# powerSMALL_smaller.net
KiCad netlist of a schematic drawn in EAGLE
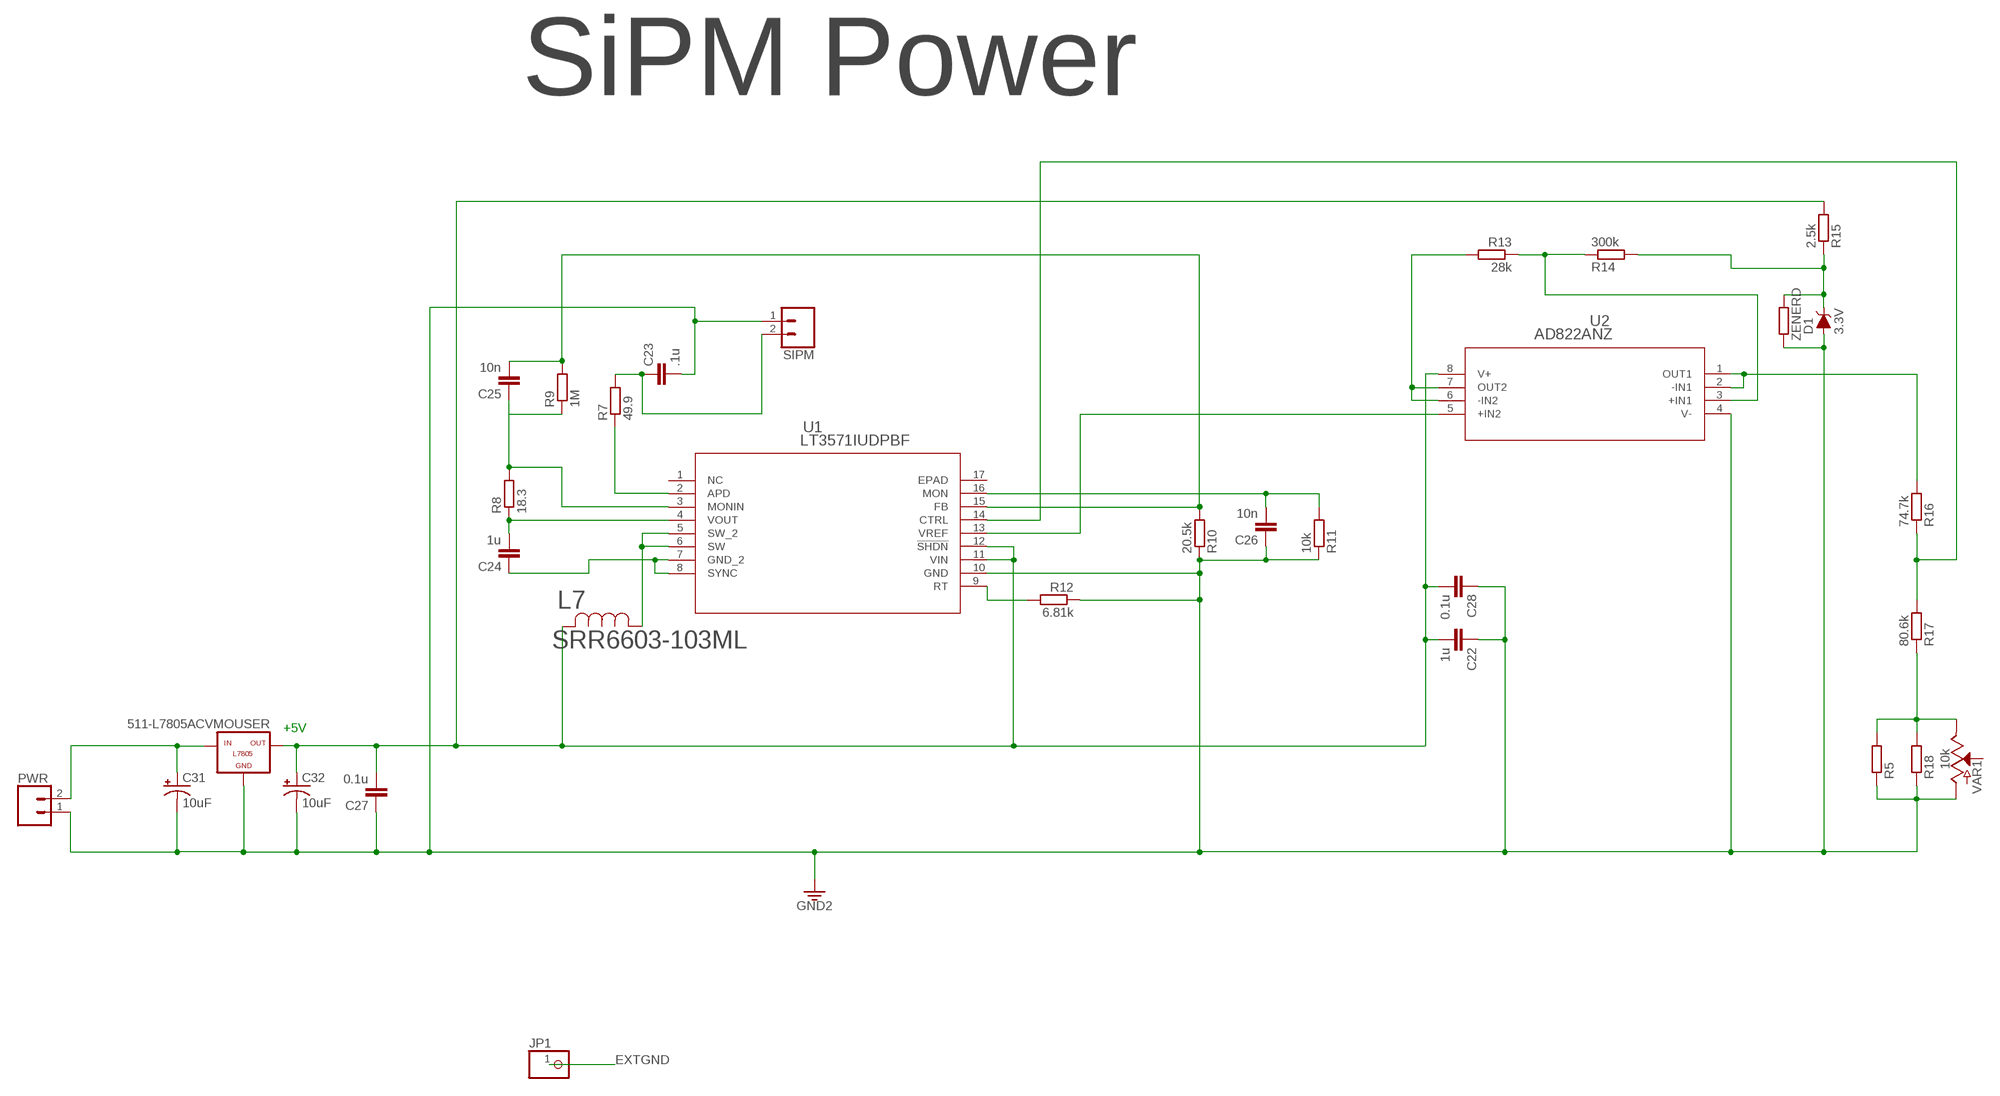
[diagram p0: schematic, sheet 1, part 1 of 2]
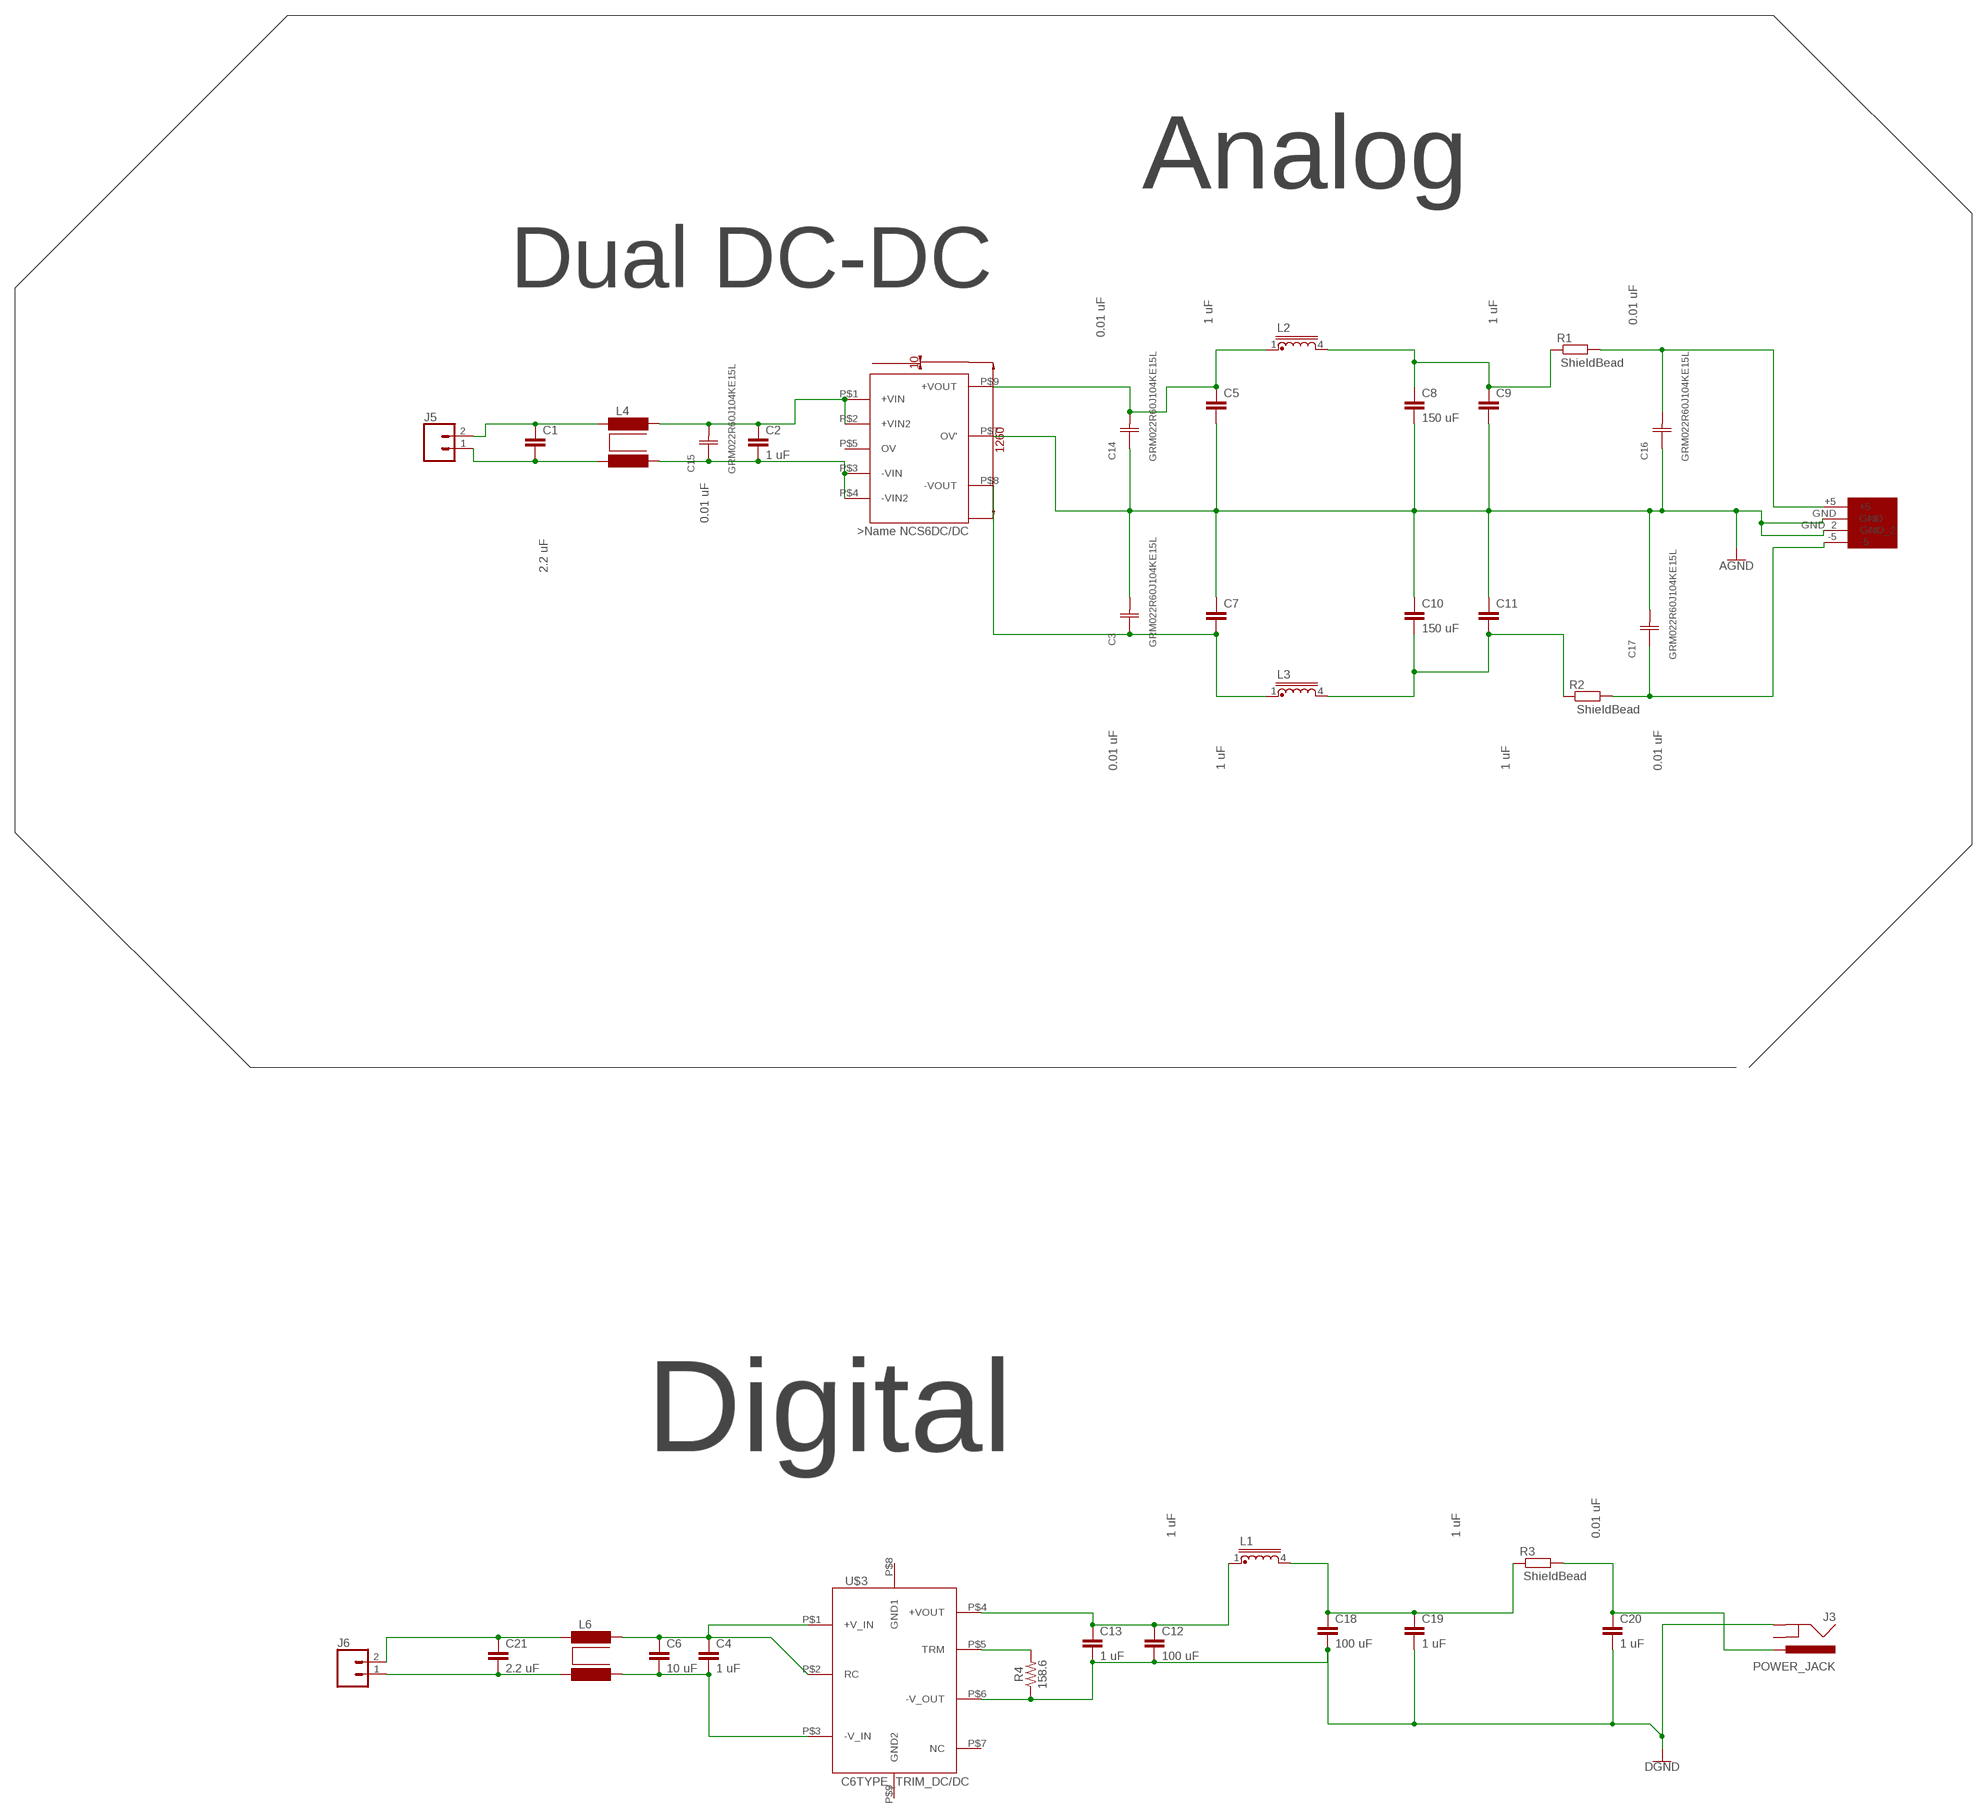
[diagram p1: schematic, sheet 1, part 2 of 2]

(export (version "E")
  (design (tool "Eeschema 10.0.6"))
  (components
    (comp (ref "511-L7805ACVMOUSER")
      (value "-L7805")
      (footprint "eagle-import:L7805")
      (libsource (lib "eagle-import") (part "-L7805"))
    )
    (comp (ref "C1")
      (value "C2.5/2")
      (footprint "eagle-import:C2.5-2")
      (libsource (lib "eagle-import") (part "C2.5/2"))
    )
    (comp (ref "C2")
      (value "1 uF")
      (footprint "eagle-import:CAP-PTH-10MM")
      (libsource (lib "eagle-import") (part "10NF-PTH-10MM-10000V-1-%"))
    )
    (comp (ref "C3")
      (value "GRM022R60J104KE15L")
      (footprint "eagle-import:CAP_GRM02L_P42XP22")
      (libsource (lib "eagle-import") (part "GRM022R60J104KE15L"))
    )
    (comp (ref "C4")
      (value "1 uF")
      (footprint "eagle-import:CAP-PTH-10MM")
      (libsource (lib "eagle-import") (part "10NF-PTH-10MM-10000V-1-%"))
    )
    (comp (ref "C5")
      (value "C2.5/2")
      (footprint "eagle-import:C2.5-2")
      (libsource (lib "eagle-import") (part "C2.5/2"))
    )
    (comp (ref "C6")
      (value "10 uF")
      (footprint "eagle-import:CAP-PTH-10MM")
      (libsource (lib "eagle-import") (part "10NF-PTH-10MM-10000V-1-%"))
    )
    (comp (ref "C7")
      (value "C2.5/2")
      (footprint "eagle-import:C2.5-2")
      (libsource (lib "eagle-import") (part "C2.5/2"))
    )
    (comp (ref "C8")
      (value "150 uF")
      (footprint "eagle-import:CAP-PTH-10MM")
      (libsource (lib "eagle-import") (part "10NF-PTH-10MM-10000V-1-%"))
    )
    (comp (ref "C9")
      (value "C2.5/2")
      (footprint "eagle-import:C2.5-2")
      (libsource (lib "eagle-import") (part "C2.5/2"))
    )
    (comp (ref "C10")
      (value "150 uF")
      (footprint "eagle-import:CAP-PTH-10MM")
      (libsource (lib "eagle-import") (part "10NF-PTH-10MM-10000V-1-%"))
    )
    (comp (ref "C11")
      (value "C2.5/2")
      (footprint "eagle-import:C2.5-2")
      (libsource (lib "eagle-import") (part "C2.5/2"))
    )
    (comp (ref "C12")
      (value "100 uF")
      (footprint "eagle-import:CAP-PTH-10MM")
      (libsource (lib "eagle-import") (part "10NF-PTH-10MM-10000V-1-%"))
    )
    (comp (ref "C13")
      (value "1 uF")
      (footprint "eagle-import:CAP-PTH-10MM")
      (libsource (lib "eagle-import") (part "10NF-PTH-10MM-10000V-1-%"))
    )
    (comp (ref "C14")
      (value "GRM022R60J104KE15L")
      (footprint "eagle-import:CAP_GRM02L_P42XP22")
      (libsource (lib "eagle-import") (part "GRM022R60J104KE15L"))
    )
    (comp (ref "C15")
      (value "GRM022R60J104KE15L")
      (footprint "eagle-import:CAP_GRM02L_P42XP22")
      (libsource (lib "eagle-import") (part "GRM022R60J104KE15L"))
    )
    (comp (ref "C16")
      (value "GRM022R60J104KE15L")
      (footprint "eagle-import:CAP_GRM02L_P42XP22")
      (libsource (lib "eagle-import") (part "GRM022R60J104KE15L"))
    )
    (comp (ref "C17")
      (value "GRM022R60J104KE15L")
      (footprint "eagle-import:CAP_GRM02L_P42XP22")
      (libsource (lib "eagle-import") (part "GRM022R60J104KE15L"))
    )
    (comp (ref "C18")
      (value "100 uF")
      (footprint "eagle-import:CAP-PTH-10MM")
      (libsource (lib "eagle-import") (part "10NF-PTH-10MM-10000V-1-%"))
    )
    (comp (ref "C19")
      (value "1 uF")
      (footprint "eagle-import:CAP-PTH-10MM")
      (libsource (lib "eagle-import") (part "10NF-PTH-10MM-10000V-1-%"))
    )
    (comp (ref "C20")
      (value "1 uF")
      (footprint "eagle-import:CAP-PTH-10MM")
      (libsource (lib "eagle-import") (part "10NF-PTH-10MM-10000V-1-%"))
    )
    (comp (ref "C21")
      (value "2.2 uF")
      (footprint "eagle-import:CAP-PTH-10MM")
      (libsource (lib "eagle-import") (part "10NF-PTH-10MM-10000V-1-%"))
    )
    (comp (ref "C22")
      (value "1u")
      (footprint "eagle-import:C2.5-2")
      (libsource (lib "eagle-import") (part "C2.5/2"))
    )
    (comp (ref "C23")
      (value ".1u")
      (footprint "eagle-import:C2.5-2")
      (libsource (lib "eagle-import") (part "C2.5/2"))
    )
    (comp (ref "C24")
      (value "1u")
      (footprint "eagle-import:C2.5-2")
      (libsource (lib "eagle-import") (part "C2.5/2"))
    )
    (comp (ref "C25")
      (value "10n")
      (footprint "eagle-import:C2.5-2")
      (libsource (lib "eagle-import") (part "C2.5/2"))
    )
    (comp (ref "C26")
      (value "10n")
      (footprint "eagle-import:C2.5-2")
      (libsource (lib "eagle-import") (part "C2.5/2"))
    )
    (comp (ref "C27")
      (value "0.1u")
      (footprint "eagle-import:C2.5-2")
      (libsource (lib "eagle-import") (part "C2.5/2"))
    )
    (comp (ref "C28")
      (value "0.1u")
      (footprint "eagle-import:C2.5-2")
      (libsource (lib "eagle-import") (part "C2.5/2"))
    )
    (comp (ref "C31")
      (value "10uF")
      (footprint "eagle-import:0603-POLAR")
      (libsource (lib "eagle-import") (part "10UF-POLAR-0603-6.3V-20%(TANT)"))
    )
    (comp (ref "C32")
      (value "10uF")
      (footprint "eagle-import:0603-POLAR")
      (libsource (lib "eagle-import") (part "10UF-POLAR-0603-6.3V-20%(TANT)"))
    )
    (comp (ref "D1")
      (value "3.3V")
      (footprint "eagle-import:SOD-323")
      (libsource (lib "eagle-import") (part "DIODE-ZENER-MM3Z3V3T1G"))
    )
    (comp (ref "J3")
      (value "POWER_JACK")
      (footprint "eagle-import:POWER_JACK_PTH")
      (libsource (lib "eagle-import") (part "POWER_JACK"))
    )
    (comp (ref "J5")
      (value "CONN_02PTH4")
      (footprint "eagle-import:1X02_XTRA_BIG")
      (libsource (lib "eagle-import") (part "CONN_02PTH4"))
    )
    (comp (ref "J6")
      (value "CONN_02PTH4")
      (footprint "eagle-import:1X02_XTRA_BIG")
      (libsource (lib "eagle-import") (part "CONN_02PTH4"))
    )
    (comp (ref "JP1")
      (value "PINHD-1X1")
      (footprint "eagle-import:1X01")
      (libsource (lib "eagle-import") (part "PINHD-1X1"))
    )
    (comp (ref "L1")
      (value "U15-CHOKE")
      (footprint "eagle-import:U15CHOKE")
      (libsource (lib "eagle-import") (part "U15-CHOKE"))
    )
    (comp (ref "L2")
      (value "U15-CHOKE")
      (footprint "eagle-import:U15CHOKE")
      (libsource (lib "eagle-import") (part "U15-CHOKE"))
    )
    (comp (ref "L3")
      (value "U15-CHOKE")
      (footprint "eagle-import:U15CHOKE")
      (libsource (lib "eagle-import") (part "U15-CHOKE"))
    )
    (comp (ref "L4")
      (value "SMR6-I")
      (footprint "eagle-import:SM-R6")
      (libsource (lib "eagle-import") (part "SMR6-I"))
    )
    (comp (ref "L6")
      (value "SMR6-I")
      (footprint "eagle-import:SM-R6")
      (libsource (lib "eagle-import") (part "SMR6-I"))
    )
    (comp (ref "L7")
      (value "SRR6603-103ML")
      (footprint "eagle-import:IND_BOURNS_SRR6603")
      (fields (field (name "MANUFACTURER_PART_NUMBER") "SRR6603103ML"))
      (libsource (lib "eagle-import") (part "SRR6603-103ML"))
    )
    (comp (ref "PWR")
      (value "CONN_02PTH4")
      (footprint "eagle-import:1X02_XTRA_BIG")
      (libsource (lib "eagle-import") (part "CONN_02PTH4"))
    )
    (comp (ref "R1")
      (value "R0207/10")
      (footprint "eagle-import:0207_10")
      (libsource (lib "eagle-import") (part "R0207/10"))
    )
    (comp (ref "R2")
      (value "R0207/10")
      (footprint "eagle-import:0207_10")
      (libsource (lib "eagle-import") (part "R0207/10"))
    )
    (comp (ref "R3")
      (value "R0207/10")
      (footprint "eagle-import:0207_10")
      (libsource (lib "eagle-import") (part "R0207/10"))
    )
    (comp (ref "R4")
      (value "158.6")
      (footprint "eagle-import:AXIAL-0.3")
      (libsource (lib "eagle-import") (part "10MOHM-HORIZ-1/4W-5%"))
    )
    (comp (ref "R5")
      (value "R0207/10")
      (footprint "eagle-import:0207_10")
      (libsource (lib "eagle-import") (part "R0207/10"))
    )
    (comp (ref "R7")
      (value "49.9")
      (footprint "eagle-import:0207_10")
      (libsource (lib "eagle-import") (part "R0207/10"))
    )
    (comp (ref "R8")
      (value "18.3")
      (footprint "eagle-import:0207_10")
      (libsource (lib "eagle-import") (part "R0207/10"))
    )
    (comp (ref "R9")
      (value "1M")
      (footprint "eagle-import:0207_10")
      (libsource (lib "eagle-import") (part "R0207/10"))
    )
    (comp (ref "R10")
      (value "20.5k")
      (footprint "eagle-import:0207_10")
      (libsource (lib "eagle-import") (part "R0207/10"))
    )
    (comp (ref "R11")
      (value "10k")
      (footprint "eagle-import:0207_10")
      (libsource (lib "eagle-import") (part "R0207/10"))
    )
    (comp (ref "R12")
      (value "6.81k")
      (footprint "eagle-import:0207_10")
      (libsource (lib "eagle-import") (part "R0207/10"))
    )
    (comp (ref "R13")
      (value "28k")
      (footprint "eagle-import:0207_10")
      (libsource (lib "eagle-import") (part "R0207/10"))
    )
    (comp (ref "R14")
      (value "300k")
      (footprint "eagle-import:0207_10")
      (libsource (lib "eagle-import") (part "R0207/10"))
    )
    (comp (ref "R15")
      (value "2.5k")
      (footprint "eagle-import:0207_10")
      (libsource (lib "eagle-import") (part "R0207/10"))
    )
    (comp (ref "R16")
      (value "74.7k")
      (footprint "eagle-import:0207_10")
      (libsource (lib "eagle-import") (part "R0207/10"))
    )
    (comp (ref "R17")
      (value "80.6k")
      (footprint "eagle-import:0207_10")
      (libsource (lib "eagle-import") (part "R0207/10"))
    )
    (comp (ref "R18")
      (value "R0207/10")
      (footprint "eagle-import:0207_10")
      (libsource (lib "eagle-import") (part "R0207/10"))
    )
    (comp (ref "SIPM")
      (value "CONN_02PTH4")
      (footprint "eagle-import:1X02_XTRA_BIG")
      (libsource (lib "eagle-import") (part "CONN_02PTH4"))
    )
    (comp (ref "U$1")
      (value "NCS6D1205")
      (footprint "eagle-import:NCS6D1205C")
      (libsource (lib "eagle-import") (part "NCS6D1205"))
    )
    (comp (ref "U$3")
      (value "C6TYPE_TRIM_DC/DC")
      (footprint "eagle-import:CONV_DC_DC_6W_SNGL_C6TYPE")
      (libsource (lib "eagle-import") (part "C6TYPE_TRIM_DC/DC"))
    )
    (comp (ref "U$4")
      (value "WM403_NDPOWER_JACK")
      (footprint "eagle-import:WM4302-ND")
      (libsource (lib "eagle-import") (part "WM403_NDPOWER_JACK"))
    )
    (comp (ref "U1")
      (value "LT3571IUDPBF")
      (footprint "eagle-import:QFN-16_UD")
      (fields (field (name "MANUFACTURER_PART_NUMBER") "LT3571IUD#PBF"))
      (libsource (lib "eagle-import") (part "LT3571IUDPBF"))
    )
    (comp (ref "U2")
      (value "AD822ANZ")
      (footprint "eagle-import:N_8")
      (libsource (lib "eagle-import") (part "AD822ANZ"))
    )
    (comp (ref "VAR1")
      (value "10k")
      (footprint "eagle-import:POT-PTH-ALPS")
      (libsource (lib "eagle-import") (part "POTENTIOMETER-PTH-9MM-1/20W-20%"))
    )
    (comp (ref "ZENERD")
      (value "R0207/10")
      (footprint "eagle-import:0207_10")
      (libsource (lib "eagle-import") (part "R0207/10"))
    )
  )
  (nets
    (net (code "1") (name "/EXTGND") (class "Default")
      (node (ref "JP1") (pin "1") (pinfunction "1_1") (pintype "passive"))
    )
    (net (code "2") (name "AGND") (class "Default")
      (node (ref "C10") (pin "1") (pinfunction "1_1") (pintype "passive"))
      (node (ref "C11") (pin "1") (pinfunction "1_1") (pintype "passive"))
      (node (ref "C14") (pin "1") (pinfunction "11_1") (pintype "passive"))
      (node (ref "C16") (pin "1") (pinfunction "11_1") (pintype "passive"))
      (node (ref "C17") (pin "2") (pinfunction "22_2") (pintype "passive"))
      (node (ref "C3") (pin "2") (pinfunction "22_2") (pintype "passive"))
      (node (ref "C5") (pin "2") (pinfunction "2_2") (pintype "passive"))
      (node (ref "C7") (pin "1") (pinfunction "1_1") (pintype "passive"))
      (node (ref "C8") (pin "2") (pinfunction "2_2") (pintype "passive"))
      (node (ref "C9") (pin "2") (pinfunction "2_2") (pintype "passive"))
      (node (ref "U$1") (pin "P$7") (pinfunction "OV'_P$7") (pintype "bidirectional"))
      (node (ref "U$4") (pin "GND") (pinfunction "GND_GND") (pintype "bidirectional"))
      (node (ref "U$4") (pin "GND_2") (pinfunction "GND_2_GND_2") (pintype "bidirectional"))
    )
    (net (code "3") (name "DGND") (class "Default")
      (node (ref "C12") (pin "2") (pinfunction "2_2") (pintype "passive"))
      (node (ref "C13") (pin "2") (pinfunction "2_2") (pintype "passive"))
      (node (ref "C18") (pin "2") (pinfunction "2_2") (pintype "passive"))
      (node (ref "C19") (pin "2") (pinfunction "2_2") (pintype "passive"))
      (node (ref "C20") (pin "2") (pinfunction "2_2") (pintype "passive"))
      (node (ref "J3") (pin "GND") (pinfunction "GND_GND") (pintype "bidirectional"))
      (node (ref "R4") (pin "P$1") (pinfunction "1_P$1") (pintype "passive"))
      (node (ref "U$3") (pin "P$6") (pinfunction "-V_OUT_P$6") (pintype "bidirectional"))
    )
    (net (code "4") (name "GND2") (class "Default")
      (node (ref "511-L7805ACVMOUSER") (pin "GND") (pinfunction "GND_GND") (pintype "input"))
      (node (ref "C22") (pin "1") (pinfunction "1_1") (pintype "passive"))
      (node (ref "C23") (pin "2") (pinfunction "2_2") (pintype "passive"))
      (node (ref "C26") (pin "1") (pinfunction "1_1") (pintype "passive"))
      (node (ref "C27") (pin "1") (pinfunction "1_1") (pintype "passive"))
      (node (ref "C28") (pin "1") (pinfunction "1_1") (pintype "passive"))
      (node (ref "C31") (pin "-") (pinfunction "-_-") (pintype "passive"))
      (node (ref "C32") (pin "-") (pinfunction "-_-") (pintype "passive"))
      (node (ref "D1") (pin "A") (pinfunction "A_A") (pintype "passive"))
      (node (ref "PWR") (pin "1") (pinfunction "1_1") (pintype "passive"))
      (node (ref "R10") (pin "1") (pinfunction "1_1") (pintype "passive"))
      (node (ref "R11") (pin "1") (pinfunction "1_1") (pintype "passive"))
      (node (ref "R12") (pin "1") (pinfunction "1_1") (pintype "passive"))
      (node (ref "R18") (pin "1") (pinfunction "1_1") (pintype "passive"))
      (node (ref "R5") (pin "1") (pinfunction "1_1") (pintype "passive"))
      (node (ref "SIPM") (pin "1") (pinfunction "1_1") (pintype "passive"))
      (node (ref "U1") (pin "10") (pinfunction "GND_10") (pintype "power_in"))
      (node (ref "U2") (pin "4") (pinfunction "V-_4") (pintype "power_in"))
      (node (ref "VAR1") (pin "P$3") (pinfunction "A_P$3") (pintype "passive"))
      (node (ref "ZENERD") (pin "1") (pinfunction "1_1") (pintype "passive"))
    )
    (net (code "5") (name "Net-(511-L7805ACVMOUSER-PadIN)") (class "Default")
      (node (ref "511-L7805ACVMOUSER") (pin "IN") (pinfunction "IN_IN") (pintype "input"))
      (node (ref "C31") (pin "+") (pinfunction "+_+") (pintype "passive"))
      (node (ref "PWR") (pin "2") (pinfunction "2_2") (pintype "passive"))
    )
    (net (code "6") (name "Net-(C1-Pad1)") (class "Default")
      (node (ref "C1") (pin "1") (pinfunction "1_1") (pintype "passive"))
      (node (ref "J5") (pin "2") (pinfunction "2_2") (pintype "passive"))
      (node (ref "L4") (pin "1") (pinfunction "1_1") (pintype "passive"))
    )
    (net (code "7") (name "Net-(C1-Pad2)") (class "Default")
      (node (ref "C1") (pin "2") (pinfunction "2_2") (pintype "passive"))
      (node (ref "J5") (pin "1") (pinfunction "1_1") (pintype "passive"))
      (node (ref "L4") (pin "4") (pinfunction "4_4") (pintype "passive"))
    )
    (net (code "8") (name "Net-(C3-11)") (class "Default")
      (node (ref "C3") (pin "1") (pinfunction "11_1") (pintype "passive"))
      (node (ref "C7") (pin "2") (pinfunction "2_2") (pintype "passive"))
      (node (ref "L3") (pin "1") (pinfunction "1_1") (pintype "passive"))
      (node (ref "U$1") (pin "P$8") (pinfunction "-VOUT_P$8") (pintype "bidirectional"))
    )
    (net (code "9") (name "Net-(C8-Pad1)") (class "Default")
      (node (ref "C8") (pin "1") (pinfunction "1_1") (pintype "passive"))
      (node (ref "C9") (pin "1") (pinfunction "1_1") (pintype "passive"))
      (node (ref "L2") (pin "4") (pinfunction "4_4") (pintype "passive"))
      (node (ref "R1") (pin "1") (pinfunction "1_1") (pintype "passive"))
    )
    (net (code "10") (name "Net-(C10-Pad2)") (class "Default")
      (node (ref "C10") (pin "2") (pinfunction "2_2") (pintype "passive"))
      (node (ref "C11") (pin "2") (pinfunction "2_2") (pintype "passive"))
      (node (ref "L3") (pin "4") (pinfunction "4_4") (pintype "passive"))
      (node (ref "R2") (pin "1") (pinfunction "1_1") (pintype "passive"))
    )
    (net (code "11") (name "Net-(C14-22)") (class "Default")
      (node (ref "C14") (pin "2") (pinfunction "22_2") (pintype "passive"))
      (node (ref "C5") (pin "1") (pinfunction "1_1") (pintype "passive"))
      (node (ref "L2") (pin "1") (pinfunction "1_1") (pintype "passive"))
      (node (ref "U$1") (pin "P$9") (pinfunction "+VOUT_P$9") (pintype "bidirectional"))
    )
    (net (code "12") (name "Net-(C15-11)") (class "Default")
      (node (ref "C15") (pin "1") (pinfunction "11_1") (pintype "passive"))
      (node (ref "C2") (pin "2") (pinfunction "2_2") (pintype "passive"))
      (node (ref "L4") (pin "5") (pinfunction "5_5") (pintype "passive"))
      (node (ref "U$1") (pin "P$3") (pinfunction "-VIN_P$3") (pintype "bidirectional"))
      (node (ref "U$1") (pin "P$4") (pinfunction "-VIN2_P$4") (pintype "bidirectional"))
    )
    (net (code "13") (name "Net-(C15-22)") (class "Default")
      (node (ref "C15") (pin "2") (pinfunction "22_2") (pintype "passive"))
      (node (ref "C2") (pin "1") (pinfunction "1_1") (pintype "passive"))
      (node (ref "L4") (pin "8") (pinfunction "8_8") (pintype "passive"))
      (node (ref "U$1") (pin "P$1") (pinfunction "+VIN_P$1") (pintype "power_in"))
      (node (ref "U$1") (pin "P$2") (pinfunction "+VIN2_P$2") (pintype "power_in"))
    )
    (net (code "14") (name "Net-(C16-22)") (class "Default")
      (node (ref "C16") (pin "2") (pinfunction "22_2") (pintype "passive"))
      (node (ref "R1") (pin "2") (pinfunction "2_2") (pintype "passive"))
      (node (ref "U$4") (pin "+5") (pinfunction "+5_+5") (pintype "bidirectional"))
    )
    (net (code "15") (name "Net-(C17-11)") (class "Default")
      (node (ref "C17") (pin "1") (pinfunction "11_1") (pintype "passive"))
      (node (ref "R2") (pin "2") (pinfunction "2_2") (pintype "passive"))
      (node (ref "U$4") (pin "-5") (pinfunction "-5_-5") (pintype "bidirectional"))
    )
    (net (code "16") (name "Net-(C18-Pad1)") (class "Default")
      (node (ref "C18") (pin "1") (pinfunction "1_1") (pintype "passive"))
      (node (ref "C19") (pin "1") (pinfunction "1_1") (pintype "passive"))
      (node (ref "L1") (pin "4") (pinfunction "4_4") (pintype "passive"))
      (node (ref "R3") (pin "1") (pinfunction "1_1") (pintype "passive"))
    )
    (net (code "17") (name "Net-(C20-Pad1)") (class "Default")
      (node (ref "C20") (pin "1") (pinfunction "1_1") (pintype "passive"))
      (node (ref "J3") (pin "PWR") (pinfunction "PWR_PWR") (pintype "bidirectional"))
      (node (ref "R3") (pin "2") (pinfunction "2_2") (pintype "passive"))
    )
    (net (code "18") (name "Net-(C21-Pad1)") (class "Default")
      (node (ref "C21") (pin "1") (pinfunction "1_1") (pintype "passive"))
      (node (ref "J6") (pin "2") (pinfunction "2_2") (pintype "passive"))
      (node (ref "L6") (pin "1") (pinfunction "1_1") (pintype "passive"))
    )
    (net (code "19") (name "Net-(C21-Pad2)") (class "Default")
      (node (ref "C21") (pin "2") (pinfunction "2_2") (pintype "passive"))
      (node (ref "J6") (pin "1") (pinfunction "1_1") (pintype "passive"))
      (node (ref "L6") (pin "4") (pinfunction "4_4") (pintype "passive"))
    )
    (net (code "20") (name "Net-(C23-Pad1)") (class "Default")
      (node (ref "C23") (pin "1") (pinfunction "1_1") (pintype "passive"))
      (node (ref "R7") (pin "2") (pinfunction "2_2") (pintype "passive"))
      (node (ref "SIPM") (pin "2") (pinfunction "2_2") (pintype "passive"))
    )
    (net (code "21") (name "Net-(D1-PadC)") (class "Default")
      (node (ref "D1") (pin "C") (pinfunction "C_C") (pintype "passive"))
      (node (ref "R14") (pin "2") (pinfunction "2_2") (pintype "passive"))
      (node (ref "R15") (pin "1") (pinfunction "1_1") (pintype "passive"))
      (node (ref "ZENERD") (pin "2") (pinfunction "2_2") (pintype "passive"))
    )
    (net (code "22") (name "Net-(R4-2)") (class "Default")
      (node (ref "R4") (pin "P$2") (pinfunction "2_P$2") (pintype "passive"))
      (node (ref "U$3") (pin "P$5") (pinfunction "TRM_P$5") (pintype "bidirectional"))
    )
    (net (code "23") (name "Net-(U$3-+VOUT)") (class "Default")
      (node (ref "C12") (pin "1") (pinfunction "1_1") (pintype "passive"))
      (node (ref "C13") (pin "1") (pinfunction "1_1") (pintype "passive"))
      (node (ref "L1") (pin "1") (pinfunction "1_1") (pintype "passive"))
      (node (ref "U$3") (pin "P$4") (pinfunction "+VOUT_P$4") (pintype "bidirectional"))
    )
    (net (code "24") (name "Net-(U$3-+V_IN)") (class "Default")
      (node (ref "C4") (pin "1") (pinfunction "1_1") (pintype "passive"))
      (node (ref "C6") (pin "1") (pinfunction "1_1") (pintype "passive"))
      (node (ref "L6") (pin "8") (pinfunction "8_8") (pintype "passive"))
      (node (ref "U$3") (pin "P$1") (pinfunction "+V_IN_P$1") (pintype "bidirectional"))
      (node (ref "U$3") (pin "P$2") (pinfunction "RC_P$2") (pintype "bidirectional"))
    )
    (net (code "25") (name "Net-(U$3--V_IN)") (class "Default")
      (node (ref "C4") (pin "2") (pinfunction "2_2") (pintype "passive"))
      (node (ref "C6") (pin "2") (pinfunction "2_2") (pintype "passive"))
      (node (ref "L6") (pin "5") (pinfunction "5_5") (pintype "passive"))
      (node (ref "U$3") (pin "P$3") (pinfunction "-V_IN_P$3") (pintype "bidirectional"))
    )
    (net (code "26") (name "Net-(U1-APD)") (class "Default")
      (node (ref "R7") (pin "1") (pinfunction "1_1") (pintype "passive"))
      (node (ref "U1") (pin "2") (pinfunction "APD_2") (pintype "passive"))
    )
    (net (code "27") (name "Net-(U1-CTRL)") (class "Default")
      (node (ref "R16") (pin "1") (pinfunction "1_1") (pintype "passive"))
      (node (ref "R17") (pin "2") (pinfunction "2_2") (pintype "passive"))
      (node (ref "U1") (pin "14") (pinfunction "CTRL_14") (pintype "output"))
    )
    (net (code "28") (name "Net-(U1-FB)") (class "Default")
      (node (ref "C25") (pin "2") (pinfunction "2_2") (pintype "passive"))
      (node (ref "R10") (pin "2") (pinfunction "2_2") (pintype "passive"))
      (node (ref "R9") (pin "2") (pinfunction "2_2") (pintype "passive"))
      (node (ref "U1") (pin "15") (pinfunction "FB_15") (pintype "output"))
    )
    (net (code "29") (name "Net-(U1-GND_2)") (class "Default")
      (node (ref "C24") (pin "1") (pinfunction "1_1") (pintype "passive"))
      (node (ref "U1") (pin "7") (pinfunction "GND_2_7") (pintype "power_in"))
      (node (ref "U1") (pin "8") (pinfunction "SYNC_8") (pintype "passive"))
    )
    (net (code "30") (name "Net-(U1-MON)") (class "Default")
      (node (ref "C26") (pin "2") (pinfunction "2_2") (pintype "passive"))
      (node (ref "R11") (pin "2") (pinfunction "2_2") (pintype "passive"))
      (node (ref "U1") (pin "16") (pinfunction "MON_16") (pintype "output"))
    )
    (net (code "31") (name "Net-(U1-MONIN)") (class "Default")
      (node (ref "C25") (pin "1") (pinfunction "1_1") (pintype "passive"))
      (node (ref "R8") (pin "2") (pinfunction "2_2") (pintype "passive"))
      (node (ref "R9") (pin "1") (pinfunction "1_1") (pintype "passive"))
      (node (ref "U1") (pin "3") (pinfunction "MONIN_3") (pintype "input"))
    )
    (net (code "32") (name "Net-(U1-RT)") (class "Default")
      (node (ref "R12") (pin "2") (pinfunction "2_2") (pintype "passive"))
      (node (ref "U1") (pin "9") (pinfunction "RT_9") (pintype "passive"))
    )
    (net (code "33") (name "Net-(U1-SW)") (class "Default")
      (node (ref "L7") (pin "1") (pinfunction "1_1") (pintype "passive"))
      (node (ref "U1") (pin "5") (pinfunction "SW_2_5") (pintype "passive"))
      (node (ref "U1") (pin "6") (pinfunction "SW_6") (pintype "passive"))
    )
    (net (code "34") (name "Net-(U1-VIN)") (class "Default")
      (node (ref "511-L7805ACVMOUSER") (pin "OUT") (pinfunction "OUT_OUT") (pintype "passive"))
      (node (ref "C22") (pin "2") (pinfunction "2_2") (pintype "passive"))
      (node (ref "C27") (pin "2") (pinfunction "2_2") (pintype "passive"))
      (node (ref "C28") (pin "2") (pinfunction "2_2") (pintype "passive"))
      (node (ref "C32") (pin "+") (pinfunction "+_+") (pintype "passive"))
      (node (ref "L7") (pin "2") (pinfunction "2_2") (pintype "passive"))
      (node (ref "R15") (pin "2") (pinfunction "2_2") (pintype "passive"))
      (node (ref "U1") (pin "11") (pinfunction "VIN_11") (pintype "input"))
      (node (ref "U1") (pin "12") (pinfunction "~{SHDN}_12") (pintype "passive"))
      (node (ref "U2") (pin "8") (pinfunction "V+_8") (pintype "power_in"))
    )
    (net (code "35") (name "Net-(U1-VOUT)") (class "Default")
      (node (ref "C24") (pin "2") (pinfunction "2_2") (pintype "passive"))
      (node (ref "R8") (pin "1") (pinfunction "1_1") (pintype "passive"))
      (node (ref "U1") (pin "4") (pinfunction "VOUT_4") (pintype "output"))
    )
    (net (code "36") (name "Net-(U1-VREF)") (class "Default")
      (node (ref "U1") (pin "13") (pinfunction "VREF_13") (pintype "output"))
      (node (ref "U2") (pin "5") (pinfunction "+IN2_5") (pintype "passive"))
    )
    (net (code "37") (name "Net-(U2-+IN1)") (class "Default")
      (node (ref "R13") (pin "1") (pinfunction "1_1") (pintype "passive"))
      (node (ref "R14") (pin "1") (pinfunction "1_1") (pintype "passive"))
      (node (ref "U2") (pin "3") (pinfunction "+IN1_3") (pintype "passive"))
    )
    (net (code "38") (name "Net-(U2--IN1)") (class "Default")
      (node (ref "R16") (pin "2") (pinfunction "2_2") (pintype "passive"))
      (node (ref "U2") (pin "1") (pinfunction "OUT1_1") (pintype "passive"))
      (node (ref "U2") (pin "2") (pinfunction "-IN1_2") (pintype "passive"))
    )
    (net (code "39") (name "Net-(U2--IN2)") (class "Default")
      (node (ref "R13") (pin "2") (pinfunction "2_2") (pintype "passive"))
      (node (ref "U2") (pin "6") (pinfunction "-IN2_6") (pintype "passive"))
      (node (ref "U2") (pin "7") (pinfunction "OUT2_7") (pintype "passive"))
    )
    (net (code "40") (name "Net-(VAR1-E)") (class "Default")
      (node (ref "R17") (pin "1") (pinfunction "1_1") (pintype "passive"))
      (node (ref "R18") (pin "2") (pinfunction "2_2") (pintype "passive"))
      (node (ref "R5") (pin "2") (pinfunction "2_2") (pintype "passive"))
      (node (ref "VAR1") (pin "P$1") (pinfunction "E_P$1") (pintype "passive"))
    )
    (net (code "41") (name "unconnected-(J3-PadGNDBREAK)") (class "Default")
      (node (ref "J3") (pin "GNDBREAK") (pinfunction "GNDBREAK_GNDBREAK") (pintype "bidirectional"))
    )
    (net (code "42") (name "unconnected-(U$1-OV-PadP$5)") (class "Default")
      (node (ref "U$1") (pin "P$5") (pinfunction "OV_P$5") (pintype "bidirectional"))
    )
    (net (code "43") (name "unconnected-(U$3-GND1-PadP$8)") (class "Default")
      (node (ref "U$3") (pin "P$8") (pinfunction "GND1_P$8") (pintype "bidirectional"))
    )
    (net (code "44") (name "unconnected-(U$3-GND2-PadP$9)") (class "Default")
      (node (ref "U$3") (pin "P$9") (pinfunction "GND2_P$9") (pintype "bidirectional"))
    )
    (net (code "45") (name "unconnected-(U$3-NC-PadP$7)") (class "Default")
      (node (ref "U$3") (pin "P$7") (pinfunction "NC_P$7") (pintype "bidirectional"))
    )
    (net (code "46") (name "unconnected-(U1-EPAD-Pad17)") (class "Default")
      (node (ref "U1") (pin "17") (pinfunction "EPAD_17") (pintype "passive"))
    )
    (net (code "47") (name "unconnected-(U1-NC-Pad1)") (class "Default")
      (node (ref "U1") (pin "1") (pinfunction "NC_1") (pintype "no_connect"))
    )
    (net (code "48") (name "unconnected-(VAR1-S-PadP$2)") (class "Default")
      (node (ref "VAR1") (pin "P$2") (pinfunction "S_P$2") (pintype "passive"))
    )
  )
)
